# V3_0.net
KiCad netlist of a schematic drawn in Altium Designer
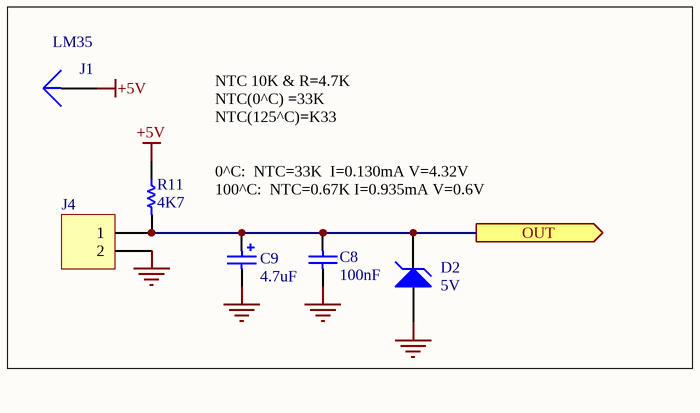
[diagram p0: V3.0.SchDoc]

(export (version "E")
  (design (tool "Eeschema 10.0.6"))
  (components
    (comp (ref "C8")
      (value "100nF")
      (footprint "CAPNTO2.54-3.05x1.78A")
      (description "Capacitor")
      (fields (field (name "MANUFACTURER") "Generic Components") (field (name "PUBLISHER") "Altium Limited"))
      (libsource (lib "Miscellaneous Devices") (part "Cap"))
    )
    (comp (ref "C9")
      (value "4.7uF")
      (footprint "CAPPR2.5-6.3x5")
      (description "Polarized Capacitor (Radial)")
      (fields (field (name "MANUFACTURER") "Generic Components") (field (name "PUBLISHER") "Altium Limited"))
      (libsource (lib "Miscellaneous Devices") (part "Cap Pol1"))
    )
    (comp (ref "D2")
      (value "5V")
      (footprint "DIODE0.4_Glass")
      (description "Zener Diode")
      (fields (field (name "MANUFACTURER") "Generic Components") (field (name "PUBLISHER") "Altium Limited"))
      (libsource (lib "Miscellaneous Devices") (part "D Zener"))
    )
    (comp (ref "J1")
      (value "COAX-M")
      (footprint "Fonics_1PIN_1")
      (description "Coax-M Connector")
      (fields (field (name "MANUFACTURER") "Generic Components") (field (name "PUBLISHER") "Altium Limited"))
      (libsource (lib "Miscellaneous Connectors") (part "COAX-M"))
    )
    (comp (ref "J4")
      (value "2PIN")
      (footprint "Fonics_2PIN_1")
      (description "Header, 2-Pin")
      (fields (field (name "PUBLISHER") "Altium Limited"))
      (libsource (lib "Miscellaneous Connectors") (part "Header 2"))
    )
    (comp (ref "R11")
      (value "4K7")
      (footprint "AXIAL-0.4")
      (description "Resistor")
      (fields (field (name "PUBLISHER") "Altium Limited"))
      (libsource (lib "Miscellaneous Devices") (part "Res1"))
    )
  )
  (nets
    (net (code "1") (name "+5V") (class "Default")
      (node (ref "J1") (pin "1") (pinfunction "A_1") (pintype "passive"))
      (node (ref "R11") (pin "1") (pinfunction "1_1") (pintype "passive"))
    )
    (net (code "2") (name "/OUT") (class "Default")
      (node (ref "C8") (pin "2") (pinfunction "2_2") (pintype "passive"))
      (node (ref "C9") (pin "1") (pinfunction "1_1") (pintype "passive"))
      (node (ref "D2") (pin "2") (pinfunction "K_2") (pintype "passive"))
      (node (ref "J4") (pin "1") (pinfunction "1_1") (pintype "passive"))
      (node (ref "R11") (pin "2") (pinfunction "2_2") (pintype "passive"))
    )
    (net (code "3") (name "GND") (class "Default")
      (node (ref "C8") (pin "1") (pinfunction "1_1") (pintype "passive"))
      (node (ref "C9") (pin "2") (pinfunction "2_2") (pintype "passive"))
      (node (ref "D2") (pin "1") (pinfunction "A_1") (pintype "passive"))
      (node (ref "J4") (pin "2") (pinfunction "2_2") (pintype "passive"))
    )
  )
)
